# Computer_Power_Relay_-_Power_Strip_E7_x.net
KiCad netlist of a schematic drawn in EAGLE
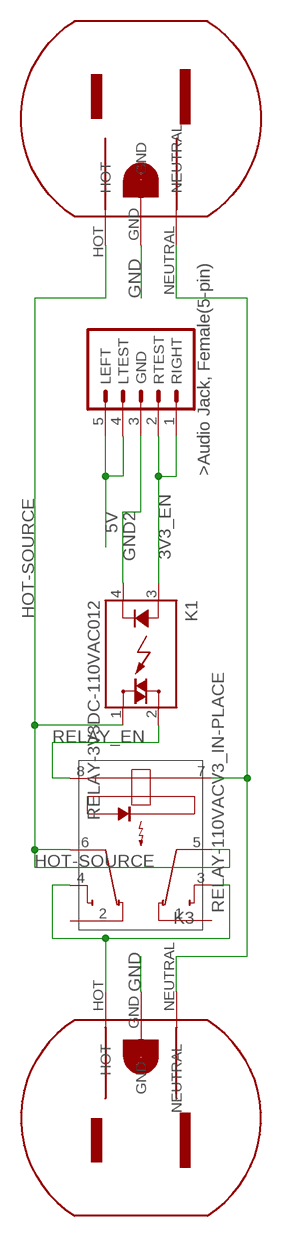
[diagram p0: schematic, sheet 1]

(export (version "E")
  (design (tool "Eeschema 10.0.6"))
  (components
    (comp (ref "K1")
      (value "RELAY-3V3DC-110VAC012")
      (footprint "eagle-import:RELAY-3V3-110V")
      (fields (field (name "MPN") "ACV33012"))
      (libsource (lib "eagle-import") (part "RELAY-3V3DC-110VAC012"))
    )
    (comp (ref "K3")
      (value "RELAY-110VACV3_IN-PLACE")
      (footprint "eagle-import:RELAY-110VAC-V3")
      (libsource (lib "eagle-import") (part "RELAY-110VACV3_IN-PLACE"))
    )
    (comp (ref "U$1")
      (value "AUDIO_JACK_FEMALE_5-PIN")
      (footprint "eagle-import:AUDIO_JACK_FEMALE_5-PIN")
      (libsource (lib "eagle-import") (part "AUDIO_JACK_FEMALE_5-PIN"))
    )
    (comp (ref "U$2")
      (value "MAINS-POWER-OUTLET3-PIN")
      (footprint "eagle-import:3-PIN-POWER")
      (libsource (lib "eagle-import") (part "MAINS-POWER-OUTLET3-PIN"))
    )
    (comp (ref "U$3")
      (value "MAINS-POWER-OUTLET3-PIN")
      (footprint "eagle-import:3-PIN-POWER")
      (libsource (lib "eagle-import") (part "MAINS-POWER-OUTLET3-PIN"))
    )
  )
  (nets
    (net (code "1") (name "/3V3_EN") (class "Default")
      (node (ref "K1") (pin "3") (pinfunction "3_3") (pintype "passive"))
      (node (ref "U$1") (pin "1") (pinfunction "RIGHT_1") (pintype "input"))
      (node (ref "U$1") (pin "2") (pinfunction "RTEST_2") (pintype "output"))
    )
    (net (code "2") (name "/5V") (class "Default")
      (node (ref "U$1") (pin "4") (pinfunction "LTEST_4") (pintype "output"))
      (node (ref "U$1") (pin "5") (pinfunction "LEFT_5") (pintype "input"))
    )
    (net (code "3") (name "/GND") (class "Default")
      (node (ref "U$2") (pin "GND") (pinfunction "GND_GND") (pintype "bidirectional"))
      (node (ref "U$3") (pin "GND") (pinfunction "GND_GND") (pintype "bidirectional"))
    )
    (net (code "4") (name "/GND2") (class "Default")
      (node (ref "K1") (pin "4") (pinfunction "4_4") (pintype "passive"))
      (node (ref "U$1") (pin "3") (pinfunction "GND_3") (pintype "power_in"))
    )
    (net (code "5") (name "/HOT-SOURCE") (class "Default")
      (node (ref "K1") (pin "1") (pinfunction "1_1") (pintype "passive"))
      (node (ref "K3") (pin "5") (pinfunction "5_5") (pintype "bidirectional"))
      (node (ref "K3") (pin "6") (pinfunction "6_6") (pintype "bidirectional"))
      (node (ref "U$3") (pin "HOT") (pinfunction "HOT_HOT") (pintype "bidirectional"))
    )
    (net (code "6") (name "/RELAY_EN") (class "Default")
      (node (ref "K1") (pin "2") (pinfunction "2_2") (pintype "passive"))
      (node (ref "K3") (pin "8") (pinfunction "8_8") (pintype "passive"))
    )
    (net (code "7") (name "Net-(K3-Pad3)") (class "Default")
      (node (ref "K3") (pin "3") (pinfunction "3_3") (pintype "bidirectional"))
      (node (ref "K3") (pin "4") (pinfunction "4_4") (pintype "bidirectional"))
      (node (ref "U$2") (pin "HOT") (pinfunction "HOT_HOT") (pintype "bidirectional"))
    )
    (net (code "8") (name "Net-(K3-Pad7)") (class "Default")
      (node (ref "K3") (pin "7") (pinfunction "7_7") (pintype "passive"))
      (node (ref "U$2") (pin "NEUTRAL") (pinfunction "NEUTRAL_NEUTRAL") (pintype "bidirectional"))
      (node (ref "U$3") (pin "NEUTRAL") (pinfunction "NEUTRAL_NEUTRAL") (pintype "bidirectional"))
    )
    (net (code "9") (name "unconnected-(K3-Pad1)") (class "Default")
      (node (ref "K3") (pin "1") (pinfunction "1_1") (pintype "bidirectional"))
    )
    (net (code "10") (name "unconnected-(K3-Pad2)") (class "Default")
      (node (ref "K3") (pin "2") (pinfunction "2_2") (pintype "bidirectional"))
    )
  )
)
